# schematic.net
KiCad netlist of a schematic drawn in EAGLE
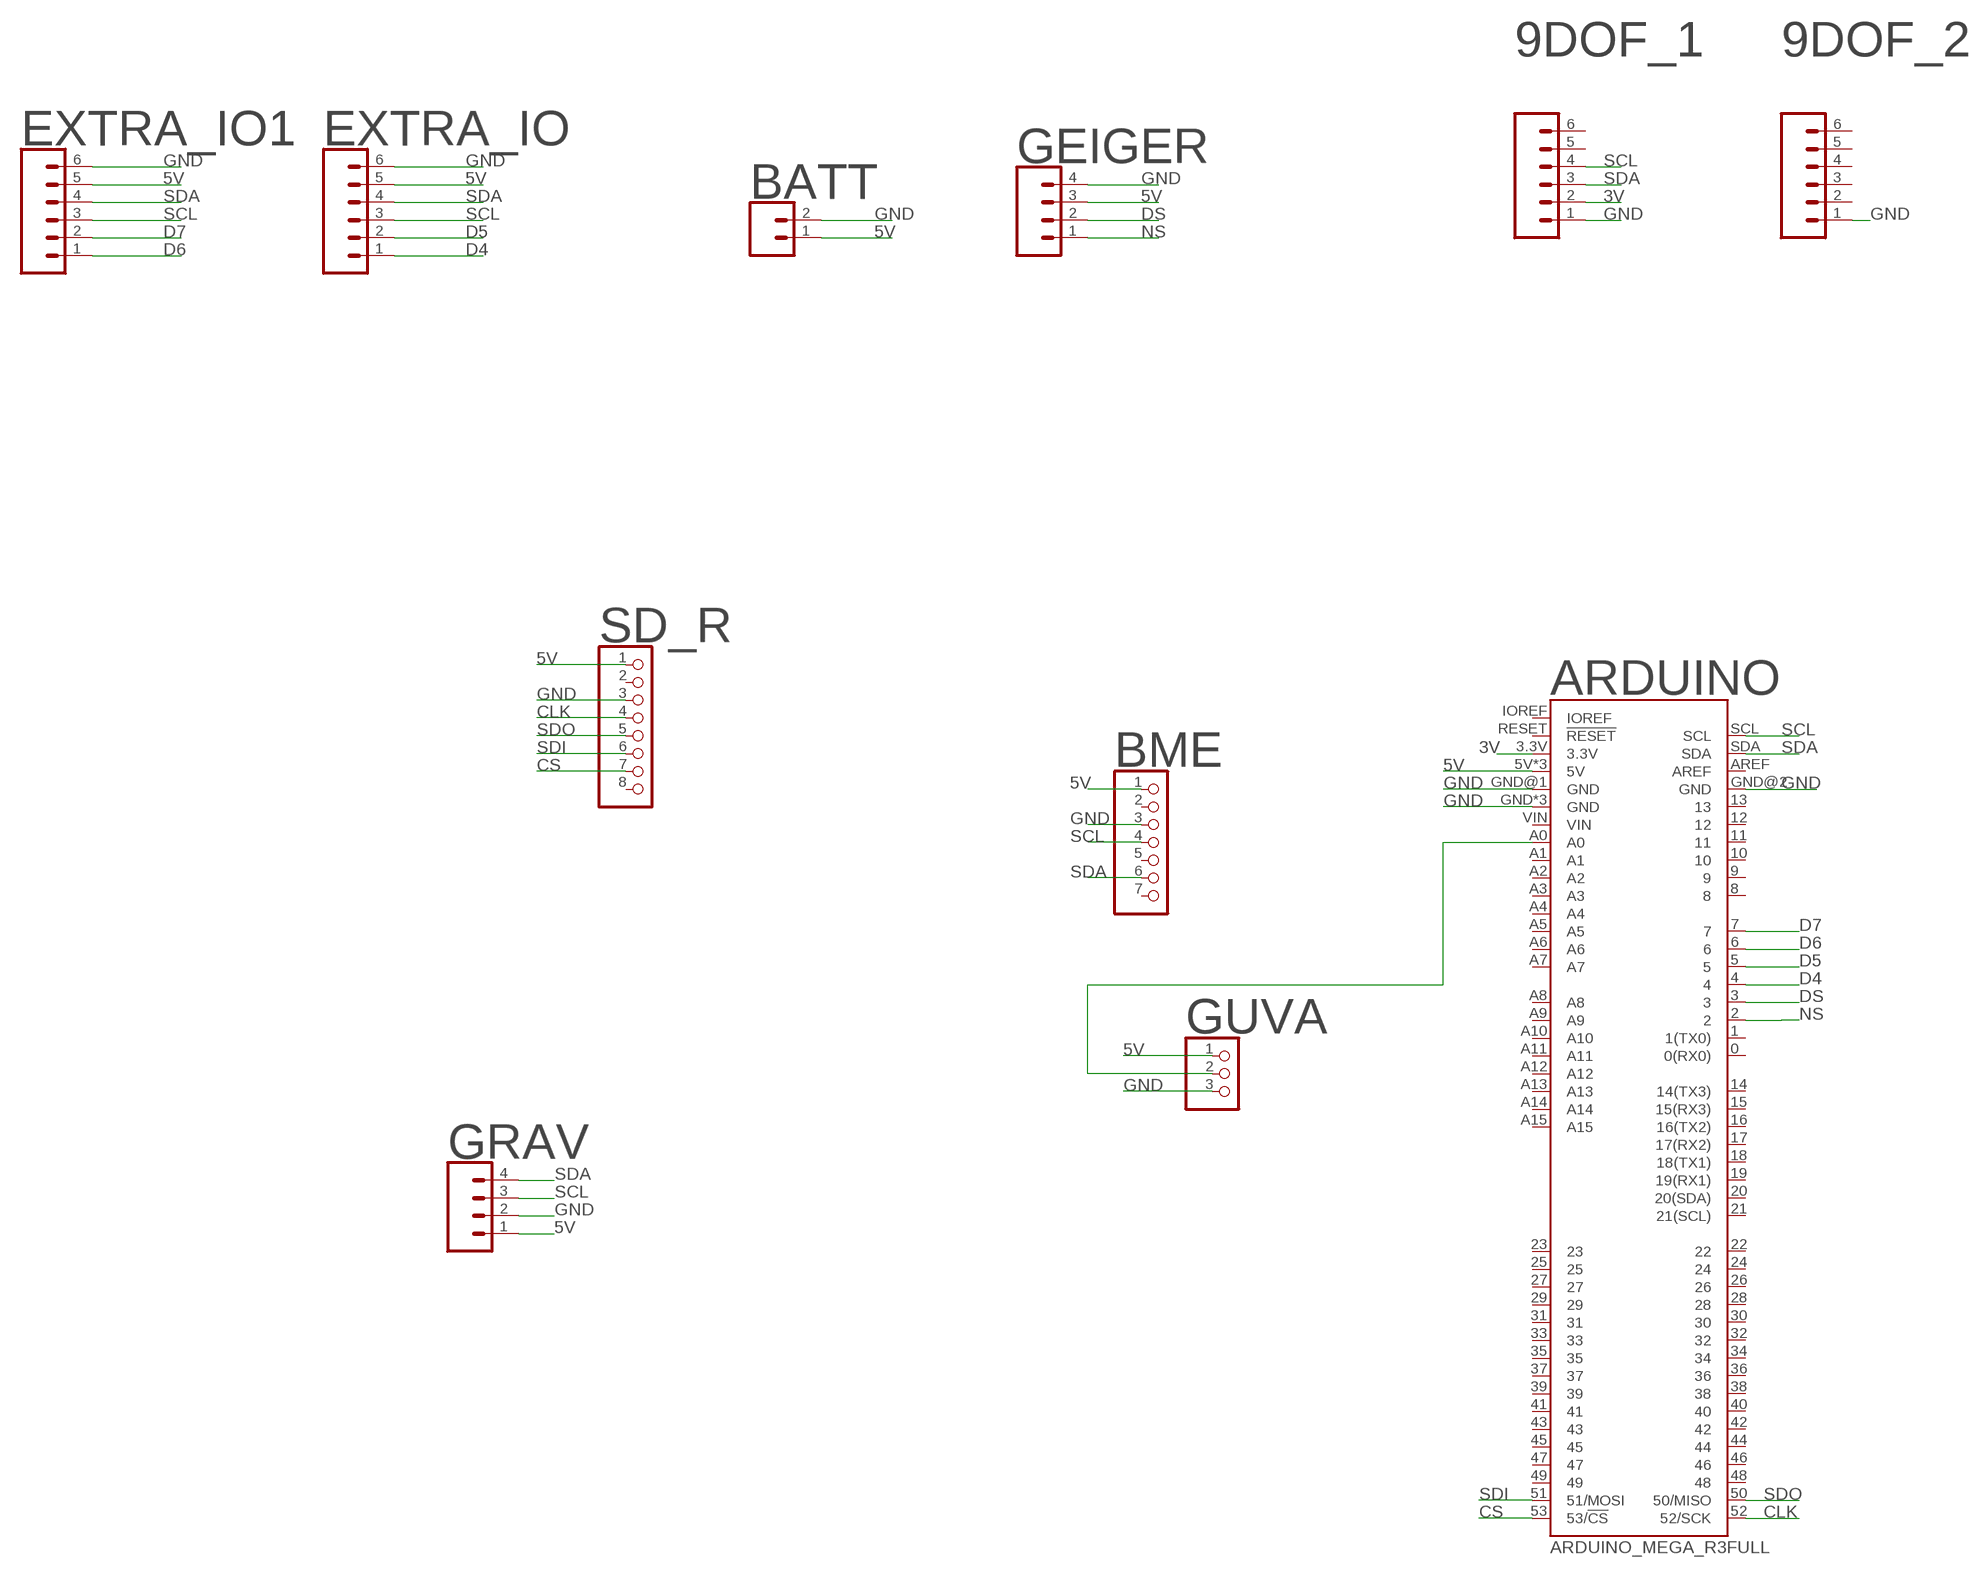
[diagram p0: schematic, sheet 1]

(export (version "E")
  (design (tool "Eeschema 10.0.6"))
  (components
    (comp (ref "9DOF_1")
      (value "CONN_06NO_SILK_NO_POP")
      (footprint "eagle-import:1X06_NO_SILK")
      (libsource (lib "eagle-import") (part "CONN_06NO_SILK_NO_POP"))
    )
    (comp (ref "9DOF_2")
      (value "CONN_06NO_SILK_NO_POP")
      (footprint "eagle-import:1X06_NO_SILK")
      (libsource (lib "eagle-import") (part "CONN_06NO_SILK_NO_POP"))
    )
    (comp (ref "ARDUINO")
      (value "ARDUINO_MEGA_R3FULL")
      (footprint "eagle-import:ARDUINO_MEGA_NO_SILK")
      (libsource (lib "eagle-import") (part "ARDUINO_MEGA_R3FULL"))
    )
    (comp (ref "BATT")
      (value "CONN_02")
      (footprint "eagle-import:1X02")
      (libsource (lib "eagle-import") (part "CONN_02"))
    )
    (comp (ref "BME")
      (value "HEADER-1X770MIL")
      (footprint "eagle-import:1X07_ROUND_70")
      (libsource (lib "eagle-import") (part "HEADER-1X770MIL"))
    )
    (comp (ref "EXTRA_IO")
      (value "CONN_06SILK_FEMALE_PTH")
      (footprint "eagle-import:1X06")
      (libsource (lib "eagle-import") (part "CONN_06SILK_FEMALE_PTH"))
    )
    (comp (ref "EXTRA_IO1")
      (value "CONN_06SILK_FEMALE_PTH")
      (footprint "eagle-import:1X06")
      (libsource (lib "eagle-import") (part "CONN_06SILK_FEMALE_PTH"))
    )
    (comp (ref "GEIGER")
      (value "CONN_04PTH")
      (footprint "eagle-import:1X04")
      (libsource (lib "eagle-import") (part "CONN_04PTH"))
    )
    (comp (ref "GRAV")
      (value "CONN_04LOCK")
      (footprint "eagle-import:1X04_LOCK")
      (libsource (lib "eagle-import") (part "CONN_04LOCK"))
    )
    (comp (ref "GUVA")
      (value "PINHD-1X3CB")
      (footprint "eagle-import:1X03-CLEANBIG")
      (libsource (lib "eagle-import") (part "PINHD-1X3CB"))
    )
    (comp (ref "SD_R")
      (value "PINHD-1X8BIG")
      (footprint "eagle-import:1X08-BIG")
      (libsource (lib "eagle-import") (part "PINHD-1X8BIG"))
    )
  )
  (nets
    (net (code "1") (name "/3V") (class "Default")
      (node (ref "9DOF_1") (pin "2") (pinfunction "2_2") (pintype "passive"))
      (node (ref "ARDUINO") (pin "3.3V") (pinfunction "3.3V_3.3V") (pintype "bidirectional"))
    )
    (net (code "2") (name "/5V") (class "Default")
      (node (ref "ARDUINO") (pin "5V") (pinfunction "5V_5V") (pintype "bidirectional"))
      (node (ref "ARDUINO") (pin "5V@1") (pinfunction "5V_5V@1") (pintype "bidirectional"))
      (node (ref "ARDUINO") (pin "5V@2") (pinfunction "5V_5V@2") (pintype "bidirectional"))
      (node (ref "BATT") (pin "1") (pinfunction "1_1") (pintype "passive"))
      (node (ref "BME") (pin "1") (pinfunction "1_1") (pintype "passive"))
      (node (ref "EXTRA_IO") (pin "5") (pinfunction "5_5") (pintype "passive"))
      (node (ref "EXTRA_IO1") (pin "5") (pinfunction "5_5") (pintype "passive"))
      (node (ref "GEIGER") (pin "3") (pinfunction "3_3") (pintype "passive"))
      (node (ref "GRAV") (pin "1") (pinfunction "1_1") (pintype "passive"))
      (node (ref "GUVA") (pin "1") (pinfunction "1_1") (pintype "passive"))
      (node (ref "SD_R") (pin "1") (pinfunction "1_1") (pintype "passive"))
    )
    (net (code "3") (name "/CLK") (class "Default")
      (node (ref "ARDUINO") (pin "52") (pinfunction "52/SCK_52") (pintype "bidirectional"))
      (node (ref "SD_R") (pin "4") (pinfunction "4_4") (pintype "passive"))
    )
    (net (code "4") (name "/CS") (class "Default")
      (node (ref "ARDUINO") (pin "53") (pinfunction "53/~{CS}_53") (pintype "bidirectional"))
      (node (ref "SD_R") (pin "7") (pinfunction "7_7") (pintype "passive"))
    )
    (net (code "5") (name "/D4") (class "Default")
      (node (ref "ARDUINO") (pin "4") (pinfunction "4_4") (pintype "bidirectional"))
      (node (ref "EXTRA_IO") (pin "1") (pinfunction "1_1") (pintype "passive"))
    )
    (net (code "6") (name "/D5") (class "Default")
      (node (ref "ARDUINO") (pin "5") (pinfunction "5_5") (pintype "bidirectional"))
      (node (ref "EXTRA_IO") (pin "2") (pinfunction "2_2") (pintype "passive"))
    )
    (net (code "7") (name "/D6") (class "Default")
      (node (ref "ARDUINO") (pin "6") (pinfunction "6_6") (pintype "bidirectional"))
      (node (ref "EXTRA_IO1") (pin "1") (pinfunction "1_1") (pintype "passive"))
    )
    (net (code "8") (name "/D7") (class "Default")
      (node (ref "ARDUINO") (pin "7") (pinfunction "7_7") (pintype "bidirectional"))
      (node (ref "EXTRA_IO1") (pin "2") (pinfunction "2_2") (pintype "passive"))
    )
    (net (code "9") (name "/DS") (class "Default")
      (node (ref "ARDUINO") (pin "3") (pinfunction "3_3") (pintype "bidirectional"))
      (node (ref "GEIGER") (pin "2") (pinfunction "2_2") (pintype "passive"))
    )
    (net (code "10") (name "/GND") (class "Default")
      (node (ref "9DOF_1") (pin "1") (pinfunction "1_1") (pintype "passive"))
      (node (ref "9DOF_2") (pin "1") (pinfunction "1_1") (pintype "passive"))
      (node (ref "ARDUINO") (pin "GND") (pinfunction "GND_GND") (pintype "bidirectional"))
      (node (ref "ARDUINO") (pin "GND@1") (pinfunction "GND_GND@1") (pintype "bidirectional"))
      (node (ref "ARDUINO") (pin "GND@2") (pinfunction "GND_GND@2") (pintype "bidirectional"))
      (node (ref "ARDUINO") (pin "GND@3") (pinfunction "GND_GND@3") (pintype "bidirectional"))
      (node (ref "ARDUINO") (pin "GND@4") (pinfunction "GND_GND@4") (pintype "bidirectional"))
      (node (ref "BATT") (pin "2") (pinfunction "2_2") (pintype "passive"))
      (node (ref "BME") (pin "3") (pinfunction "3_3") (pintype "passive"))
      (node (ref "EXTRA_IO") (pin "6") (pinfunction "6_6") (pintype "passive"))
      (node (ref "EXTRA_IO1") (pin "6") (pinfunction "6_6") (pintype "passive"))
      (node (ref "GEIGER") (pin "4") (pinfunction "4_4") (pintype "passive"))
      (node (ref "GRAV") (pin "2") (pinfunction "2_2") (pintype "passive"))
      (node (ref "GUVA") (pin "3") (pinfunction "3_3") (pintype "passive"))
      (node (ref "SD_R") (pin "3") (pinfunction "3_3") (pintype "passive"))
    )
    (net (code "11") (name "/NS") (class "Default")
      (node (ref "ARDUINO") (pin "2") (pinfunction "2_2") (pintype "bidirectional"))
      (node (ref "GEIGER") (pin "1") (pinfunction "1_1") (pintype "passive"))
    )
    (net (code "12") (name "/SCL") (class "Default")
      (node (ref "9DOF_1") (pin "4") (pinfunction "4_4") (pintype "passive"))
      (node (ref "ARDUINO") (pin "SCL") (pinfunction "SCL_SCL") (pintype "bidirectional"))
      (node (ref "BME") (pin "4") (pinfunction "4_4") (pintype "passive"))
      (node (ref "EXTRA_IO") (pin "3") (pinfunction "3_3") (pintype "passive"))
      (node (ref "EXTRA_IO1") (pin "3") (pinfunction "3_3") (pintype "passive"))
      (node (ref "GRAV") (pin "3") (pinfunction "3_3") (pintype "passive"))
    )
    (net (code "13") (name "/SDA") (class "Default")
      (node (ref "9DOF_1") (pin "3") (pinfunction "3_3") (pintype "passive"))
      (node (ref "ARDUINO") (pin "SDA") (pinfunction "SDA_SDA") (pintype "bidirectional"))
      (node (ref "BME") (pin "6") (pinfunction "6_6") (pintype "passive"))
      (node (ref "EXTRA_IO") (pin "4") (pinfunction "4_4") (pintype "passive"))
      (node (ref "EXTRA_IO1") (pin "4") (pinfunction "4_4") (pintype "passive"))
      (node (ref "GRAV") (pin "4") (pinfunction "4_4") (pintype "passive"))
    )
    (net (code "14") (name "/SDI") (class "Default")
      (node (ref "ARDUINO") (pin "51") (pinfunction "51/MOSI_51") (pintype "bidirectional"))
      (node (ref "SD_R") (pin "6") (pinfunction "6_6") (pintype "passive"))
    )
    (net (code "15") (name "/SDO") (class "Default")
      (node (ref "ARDUINO") (pin "50") (pinfunction "50/MISO_50") (pintype "bidirectional"))
      (node (ref "SD_R") (pin "5") (pinfunction "5_5") (pintype "passive"))
    )
    (net (code "16") (name "Net-(ARDUINO-PadA0)") (class "Default")
      (node (ref "ARDUINO") (pin "A0") (pinfunction "A0_A0") (pintype "bidirectional"))
      (node (ref "GUVA") (pin "2") (pinfunction "2_2") (pintype "passive"))
    )
    (net (code "17") (name "unconnected-(9DOF_1-Pad5)") (class "Default")
      (node (ref "9DOF_1") (pin "5") (pinfunction "5_5") (pintype "passive"))
    )
    (net (code "18") (name "unconnected-(9DOF_1-Pad6)") (class "Default")
      (node (ref "9DOF_1") (pin "6") (pinfunction "6_6") (pintype "passive"))
    )
    (net (code "19") (name "unconnected-(9DOF_2-Pad2)") (class "Default")
      (node (ref "9DOF_2") (pin "2") (pinfunction "2_2") (pintype "passive"))
    )
    (net (code "20") (name "unconnected-(9DOF_2-Pad3)") (class "Default")
      (node (ref "9DOF_2") (pin "3") (pinfunction "3_3") (pintype "passive"))
    )
    (net (code "21") (name "unconnected-(9DOF_2-Pad4)") (class "Default")
      (node (ref "9DOF_2") (pin "4") (pinfunction "4_4") (pintype "passive"))
    )
    (net (code "22") (name "unconnected-(9DOF_2-Pad5)") (class "Default")
      (node (ref "9DOF_2") (pin "5") (pinfunction "5_5") (pintype "passive"))
    )
    (net (code "23") (name "unconnected-(9DOF_2-Pad6)") (class "Default")
      (node (ref "9DOF_2") (pin "6") (pinfunction "6_6") (pintype "passive"))
    )
    (net (code "24") (name "unconnected-(ARDUINO-0(RX0)-Pad0)") (class "Default")
      (node (ref "ARDUINO") (pin "0") (pinfunction "0(RX0)_0") (pintype "bidirectional"))
    )
    (net (code "25") (name "unconnected-(ARDUINO-1(TX0)-Pad1)") (class "Default")
      (node (ref "ARDUINO") (pin "1") (pinfunction "1(TX0)_1") (pintype "bidirectional"))
    )
    (net (code "26") (name "unconnected-(ARDUINO-14(TX3)-Pad14)") (class "Default")
      (node (ref "ARDUINO") (pin "14") (pinfunction "14(TX3)_14") (pintype "bidirectional"))
    )
    (net (code "27") (name "unconnected-(ARDUINO-15(RX3)-Pad15)") (class "Default")
      (node (ref "ARDUINO") (pin "15") (pinfunction "15(RX3)_15") (pintype "bidirectional"))
    )
    (net (code "28") (name "unconnected-(ARDUINO-16(TX2)-Pad16)") (class "Default")
      (node (ref "ARDUINO") (pin "16") (pinfunction "16(TX2)_16") (pintype "bidirectional"))
    )
    (net (code "29") (name "unconnected-(ARDUINO-17(RX2)-Pad17)") (class "Default")
      (node (ref "ARDUINO") (pin "17") (pinfunction "17(RX2)_17") (pintype "bidirectional"))
    )
    (net (code "30") (name "unconnected-(ARDUINO-18(TX1)-Pad18)") (class "Default")
      (node (ref "ARDUINO") (pin "18") (pinfunction "18(TX1)_18") (pintype "bidirectional"))
    )
    (net (code "31") (name "unconnected-(ARDUINO-19(RX1)-Pad19)") (class "Default")
      (node (ref "ARDUINO") (pin "19") (pinfunction "19(RX1)_19") (pintype "bidirectional"))
    )
    (net (code "32") (name "unconnected-(ARDUINO-20(SDA)-Pad20)") (class "Default")
      (node (ref "ARDUINO") (pin "20") (pinfunction "20(SDA)_20") (pintype "bidirectional"))
    )
    (net (code "33") (name "unconnected-(ARDUINO-21(SCL)-Pad21)") (class "Default")
      (node (ref "ARDUINO") (pin "21") (pinfunction "21(SCL)_21") (pintype "bidirectional"))
    )
    (net (code "34") (name "unconnected-(ARDUINO-Pad8)") (class "Default")
      (node (ref "ARDUINO") (pin "8") (pinfunction "8_8") (pintype "bidirectional"))
    )
    (net (code "35") (name "unconnected-(ARDUINO-Pad9)") (class "Default")
      (node (ref "ARDUINO") (pin "9") (pinfunction "9_9") (pintype "bidirectional"))
    )
    (net (code "36") (name "unconnected-(ARDUINO-Pad10)") (class "Default")
      (node (ref "ARDUINO") (pin "10") (pinfunction "10_10") (pintype "bidirectional"))
    )
    (net (code "37") (name "unconnected-(ARDUINO-Pad11)") (class "Default")
      (node (ref "ARDUINO") (pin "11") (pinfunction "11_11") (pintype "bidirectional"))
    )
    (net (code "38") (name "unconnected-(ARDUINO-Pad12)") (class "Default")
      (node (ref "ARDUINO") (pin "12") (pinfunction "12_12") (pintype "bidirectional"))
    )
    (net (code "39") (name "unconnected-(ARDUINO-Pad13)") (class "Default")
      (node (ref "ARDUINO") (pin "13") (pinfunction "13_13") (pintype "bidirectional"))
    )
    (net (code "40") (name "unconnected-(ARDUINO-Pad22)") (class "Default")
      (node (ref "ARDUINO") (pin "22") (pinfunction "22_22") (pintype "bidirectional"))
    )
    (net (code "41") (name "unconnected-(ARDUINO-Pad23)") (class "Default")
      (node (ref "ARDUINO") (pin "23") (pinfunction "23_23") (pintype "bidirectional"))
    )
    (net (code "42") (name "unconnected-(ARDUINO-Pad24)") (class "Default")
      (node (ref "ARDUINO") (pin "24") (pinfunction "24_24") (pintype "bidirectional"))
    )
    (net (code "43") (name "unconnected-(ARDUINO-Pad25)") (class "Default")
      (node (ref "ARDUINO") (pin "25") (pinfunction "25_25") (pintype "bidirectional"))
    )
    (net (code "44") (name "unconnected-(ARDUINO-Pad26)") (class "Default")
      (node (ref "ARDUINO") (pin "26") (pinfunction "26_26") (pintype "bidirectional"))
    )
    (net (code "45") (name "unconnected-(ARDUINO-Pad27)") (class "Default")
      (node (ref "ARDUINO") (pin "27") (pinfunction "27_27") (pintype "bidirectional"))
    )
    (net (code "46") (name "unconnected-(ARDUINO-Pad28)") (class "Default")
      (node (ref "ARDUINO") (pin "28") (pinfunction "28_28") (pintype "bidirectional"))
    )
    (net (code "47") (name "unconnected-(ARDUINO-Pad29)") (class "Default")
      (node (ref "ARDUINO") (pin "29") (pinfunction "29_29") (pintype "bidirectional"))
    )
    (net (code "48") (name "unconnected-(ARDUINO-Pad30)") (class "Default")
      (node (ref "ARDUINO") (pin "30") (pinfunction "30_30") (pintype "bidirectional"))
    )
    (net (code "49") (name "unconnected-(ARDUINO-Pad31)") (class "Default")
      (node (ref "ARDUINO") (pin "31") (pinfunction "31_31") (pintype "bidirectional"))
    )
    (net (code "50") (name "unconnected-(ARDUINO-Pad32)") (class "Default")
      (node (ref "ARDUINO") (pin "32") (pinfunction "32_32") (pintype "bidirectional"))
    )
    (net (code "51") (name "unconnected-(ARDUINO-Pad33)") (class "Default")
      (node (ref "ARDUINO") (pin "33") (pinfunction "33_33") (pintype "bidirectional"))
    )
    (net (code "52") (name "unconnected-(ARDUINO-Pad34)") (class "Default")
      (node (ref "ARDUINO") (pin "34") (pinfunction "34_34") (pintype "bidirectional"))
    )
    (net (code "53") (name "unconnected-(ARDUINO-Pad35)") (class "Default")
      (node (ref "ARDUINO") (pin "35") (pinfunction "35_35") (pintype "bidirectional"))
    )
    (net (code "54") (name "unconnected-(ARDUINO-Pad36)") (class "Default")
      (node (ref "ARDUINO") (pin "36") (pinfunction "36_36") (pintype "bidirectional"))
    )
    (net (code "55") (name "unconnected-(ARDUINO-Pad37)") (class "Default")
      (node (ref "ARDUINO") (pin "37") (pinfunction "37_37") (pintype "bidirectional"))
    )
    (net (code "56") (name "unconnected-(ARDUINO-Pad38)") (class "Default")
      (node (ref "ARDUINO") (pin "38") (pinfunction "38_38") (pintype "bidirectional"))
    )
    (net (code "57") (name "unconnected-(ARDUINO-Pad39)") (class "Default")
      (node (ref "ARDUINO") (pin "39") (pinfunction "39_39") (pintype "bidirectional"))
    )
    (net (code "58") (name "unconnected-(ARDUINO-Pad40)") (class "Default")
      (node (ref "ARDUINO") (pin "40") (pinfunction "40_40") (pintype "bidirectional"))
    )
    (net (code "59") (name "unconnected-(ARDUINO-Pad41)") (class "Default")
      (node (ref "ARDUINO") (pin "41") (pinfunction "41_41") (pintype "bidirectional"))
    )
    (net (code "60") (name "unconnected-(ARDUINO-Pad42)") (class "Default")
      (node (ref "ARDUINO") (pin "42") (pinfunction "42_42") (pintype "bidirectional"))
    )
    (net (code "61") (name "unconnected-(ARDUINO-Pad43)") (class "Default")
      (node (ref "ARDUINO") (pin "43") (pinfunction "43_43") (pintype "bidirectional"))
    )
    (net (code "62") (name "unconnected-(ARDUINO-Pad44)") (class "Default")
      (node (ref "ARDUINO") (pin "44") (pinfunction "44_44") (pintype "bidirectional"))
    )
    (net (code "63") (name "unconnected-(ARDUINO-Pad45)") (class "Default")
      (node (ref "ARDUINO") (pin "45") (pinfunction "45_45") (pintype "bidirectional"))
    )
    (net (code "64") (name "unconnected-(ARDUINO-Pad46)") (class "Default")
      (node (ref "ARDUINO") (pin "46") (pinfunction "46_46") (pintype "bidirectional"))
    )
    (net (code "65") (name "unconnected-(ARDUINO-Pad47)") (class "Default")
      (node (ref "ARDUINO") (pin "47") (pinfunction "47_47") (pintype "bidirectional"))
    )
    (net (code "66") (name "unconnected-(ARDUINO-Pad48)") (class "Default")
      (node (ref "ARDUINO") (pin "48") (pinfunction "48_48") (pintype "bidirectional"))
    )
    (net (code "67") (name "unconnected-(ARDUINO-Pad49)") (class "Default")
      (node (ref "ARDUINO") (pin "49") (pinfunction "49_49") (pintype "bidirectional"))
    )
    (net (code "68") (name "unconnected-(ARDUINO-PadA1)") (class "Default")
      (node (ref "ARDUINO") (pin "A1") (pinfunction "A1_A1") (pintype "bidirectional"))
    )
    (net (code "69") (name "unconnected-(ARDUINO-PadA2)") (class "Default")
      (node (ref "ARDUINO") (pin "A2") (pinfunction "A2_A2") (pintype "bidirectional"))
    )
    (net (code "70") (name "unconnected-(ARDUINO-PadA3)") (class "Default")
      (node (ref "ARDUINO") (pin "A3") (pinfunction "A3_A3") (pintype "bidirectional"))
    )
    (net (code "71") (name "unconnected-(ARDUINO-PadA4)") (class "Default")
      (node (ref "ARDUINO") (pin "A4") (pinfunction "A4_A4") (pintype "bidirectional"))
    )
    (net (code "72") (name "unconnected-(ARDUINO-PadA5)") (class "Default")
      (node (ref "ARDUINO") (pin "A5") (pinfunction "A5_A5") (pintype "bidirectional"))
    )
    (net (code "73") (name "unconnected-(ARDUINO-PadA6)") (class "Default")
      (node (ref "ARDUINO") (pin "A6") (pinfunction "A6_A6") (pintype "bidirectional"))
    )
    (net (code "74") (name "unconnected-(ARDUINO-PadA7)") (class "Default")
      (node (ref "ARDUINO") (pin "A7") (pinfunction "A7_A7") (pintype "bidirectional"))
    )
    (net (code "75") (name "unconnected-(ARDUINO-PadA8)") (class "Default")
      (node (ref "ARDUINO") (pin "A8") (pinfunction "A8_A8") (pintype "bidirectional"))
    )
    (net (code "76") (name "unconnected-(ARDUINO-PadA9)") (class "Default")
      (node (ref "ARDUINO") (pin "A9") (pinfunction "A9_A9") (pintype "bidirectional"))
    )
    (net (code "77") (name "unconnected-(ARDUINO-PadA10)") (class "Default")
      (node (ref "ARDUINO") (pin "A10") (pinfunction "A10_A10") (pintype "bidirectional"))
    )
    (net (code "78") (name "unconnected-(ARDUINO-PadA11)") (class "Default")
      (node (ref "ARDUINO") (pin "A11") (pinfunction "A11_A11") (pintype "bidirectional"))
    )
    (net (code "79") (name "unconnected-(ARDUINO-PadA12)") (class "Default")
      (node (ref "ARDUINO") (pin "A12") (pinfunction "A12_A12") (pintype "bidirectional"))
    )
    (net (code "80") (name "unconnected-(ARDUINO-PadA13)") (class "Default")
      (node (ref "ARDUINO") (pin "A13") (pinfunction "A13_A13") (pintype "bidirectional"))
    )
    (net (code "81") (name "unconnected-(ARDUINO-PadA14)") (class "Default")
      (node (ref "ARDUINO") (pin "A14") (pinfunction "A14_A14") (pintype "bidirectional"))
    )
    (net (code "82") (name "unconnected-(ARDUINO-PadA15)") (class "Default")
      (node (ref "ARDUINO") (pin "A15") (pinfunction "A15_A15") (pintype "bidirectional"))
    )
    (net (code "83") (name "unconnected-(ARDUINO-PadAREF)") (class "Default")
      (node (ref "ARDUINO") (pin "AREF") (pinfunction "AREF_AREF") (pintype "bidirectional"))
    )
    (net (code "84") (name "unconnected-(ARDUINO-PadIOREF)") (class "Default")
      (node (ref "ARDUINO") (pin "IOREF") (pinfunction "IOREF_IOREF") (pintype "bidirectional"))
    )
    (net (code "85") (name "unconnected-(ARDUINO-PadVIN)") (class "Default")
      (node (ref "ARDUINO") (pin "VIN") (pinfunction "VIN_VIN") (pintype "bidirectional"))
    )
    (net (code "86") (name "unconnected-(ARDUINO-~{RESET}-PadRESET)") (class "Default")
      (node (ref "ARDUINO") (pin "RESET") (pinfunction "~{RESET}_RESET") (pintype "bidirectional"))
    )
    (net (code "87") (name "unconnected-(BME-Pad2)") (class "Default")
      (node (ref "BME") (pin "2") (pinfunction "2_2") (pintype "passive"))
    )
    (net (code "88") (name "unconnected-(BME-Pad5)") (class "Default")
      (node (ref "BME") (pin "5") (pinfunction "5_5") (pintype "passive"))
    )
    (net (code "89") (name "unconnected-(BME-Pad7)") (class "Default")
      (node (ref "BME") (pin "7") (pinfunction "7_7") (pintype "passive"))
    )
    (net (code "90") (name "unconnected-(SD_R-Pad2)") (class "Default")
      (node (ref "SD_R") (pin "2") (pinfunction "2_2") (pintype "passive"))
    )
    (net (code "91") (name "unconnected-(SD_R-Pad8)") (class "Default")
      (node (ref "SD_R") (pin "8") (pinfunction "8_8") (pintype "passive"))
    )
  )
)
